# openSX70-bench-new-v2-1.net
KiCad netlist of a schematic drawn in EAGLE
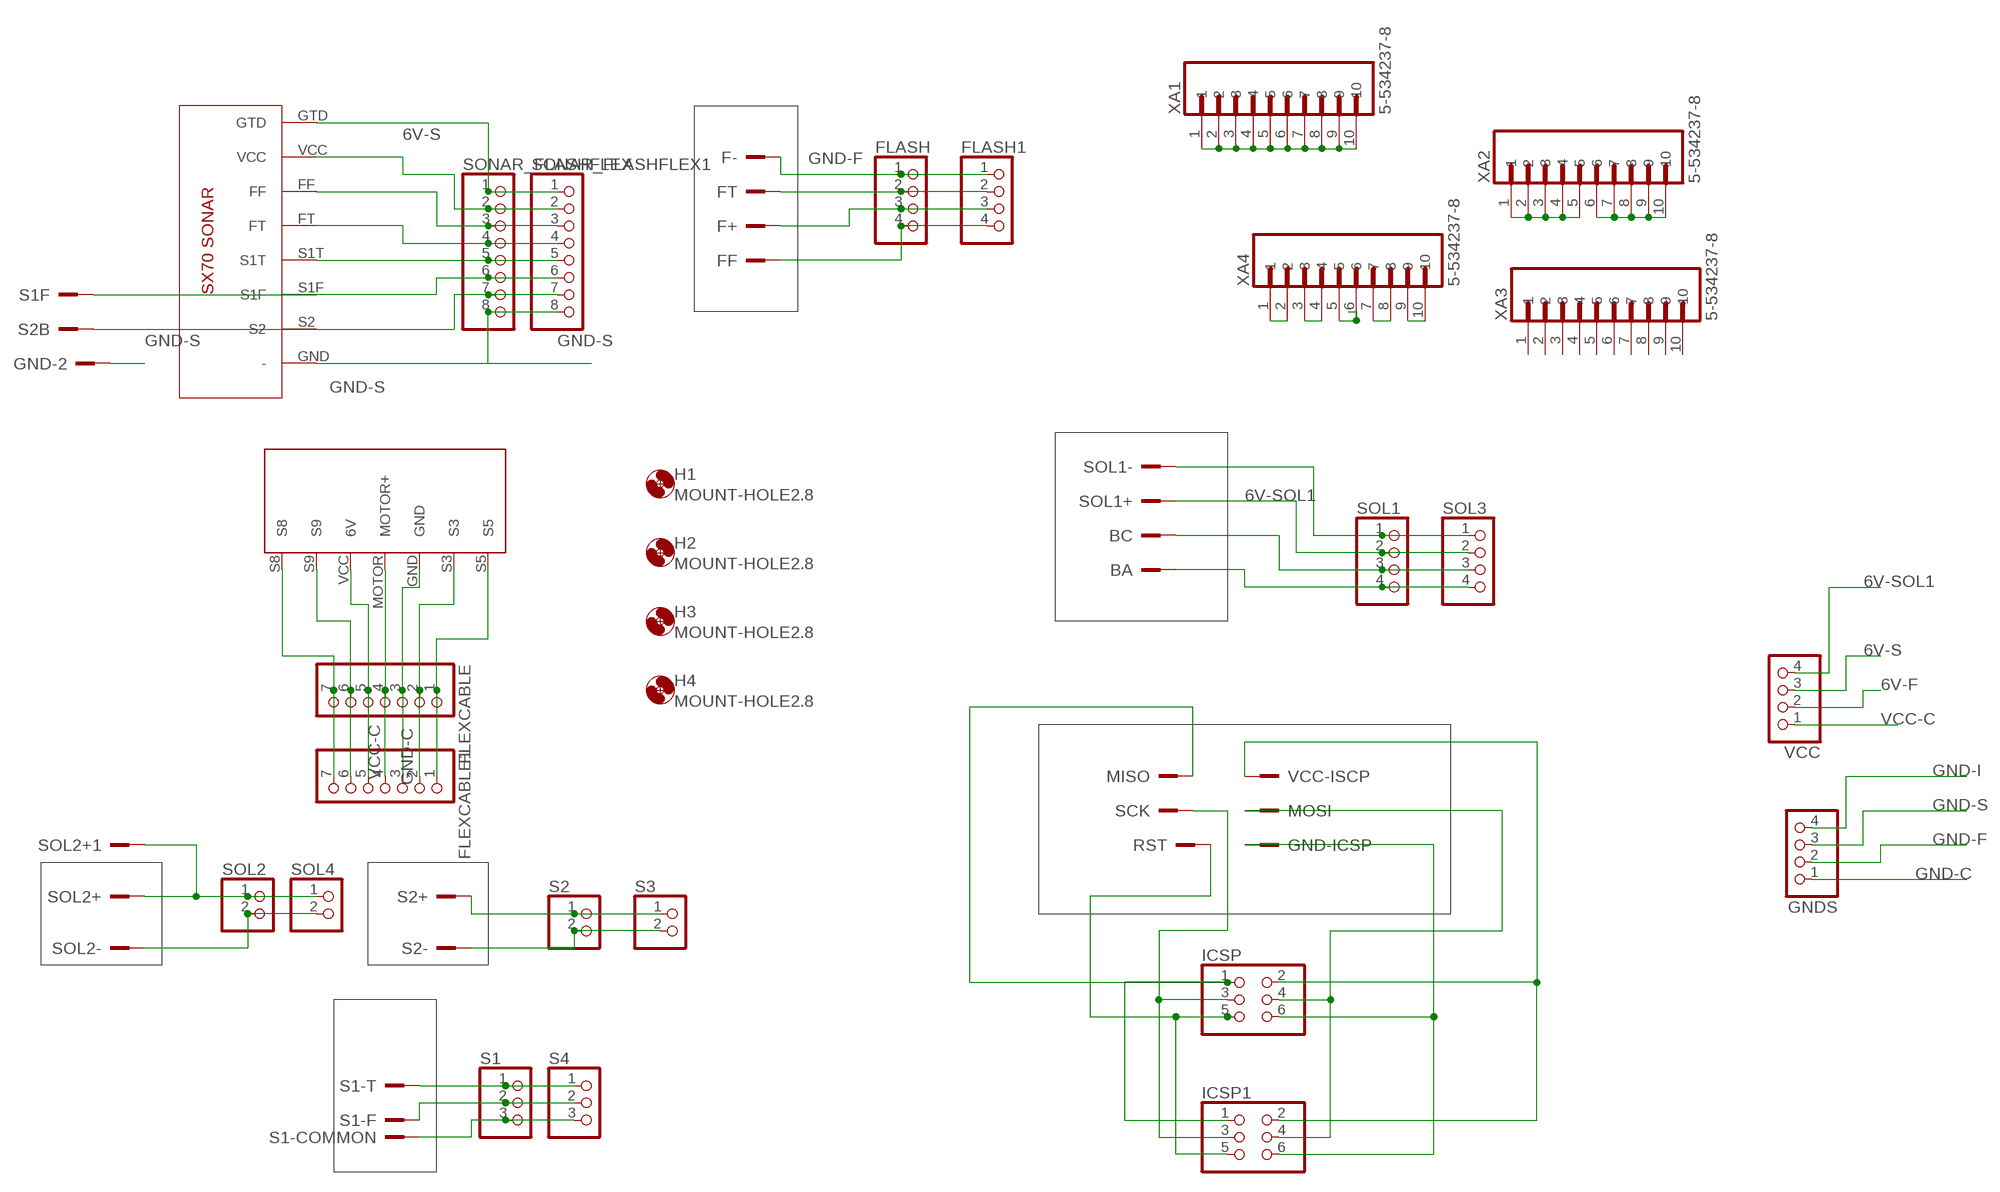
[diagram p0: schematic, sheet 1]

(export (version "E")
  (design (tool "Eeschema 10.0.6"))
  (components
    (comp (ref "BA")
      (value "PINHEAD")
      (footprint "eagle-import:1X01")
      (libsource (lib "eagle-import") (part "PINHEAD"))
    )
    (comp (ref "BC")
      (value "PINHEAD")
      (footprint "eagle-import:1X01")
      (libsource (lib "eagle-import") (part "PINHEAD"))
    )
    (comp (ref "F+")
      (value "PINHEAD")
      (footprint "eagle-import:1X01")
      (libsource (lib "eagle-import") (part "PINHEAD"))
    )
    (comp (ref "F-")
      (value "PINHEAD")
      (footprint "eagle-import:1X01")
      (libsource (lib "eagle-import") (part "PINHEAD"))
    )
    (comp (ref "FF")
      (value "PINHEAD")
      (footprint "eagle-import:1X01")
      (libsource (lib "eagle-import") (part "PINHEAD"))
    )
    (comp (ref "FLASH")
      (value "PINHD-1X4")
      (footprint "eagle-import:1X04")
      (libsource (lib "eagle-import") (part "PINHD-1X4"))
    )
    (comp (ref "FLASH1")
      (value "PINHD-1X4")
      (footprint "eagle-import:1X04")
      (libsource (lib "eagle-import") (part "PINHD-1X4"))
    )
    (comp (ref "FLEXCABLE")
      (value "PINHD-1X7")
      (footprint "eagle-import:1X07")
      (libsource (lib "eagle-import") (part "PINHD-1X7"))
    )
    (comp (ref "FLEXCABLE1")
      (value "PINHD-1X7")
      (footprint "eagle-import:1X07")
      (libsource (lib "eagle-import") (part "PINHD-1X7"))
    )
    (comp (ref "FT")
      (value "PINHEAD")
      (footprint "eagle-import:1X01")
      (libsource (lib "eagle-import") (part "PINHEAD"))
    )
    (comp (ref "GND-2")
      (value "PINHEAD")
      (footprint "eagle-import:1X01")
      (libsource (lib "eagle-import") (part "PINHEAD"))
    )
    (comp (ref "GND-ICSP")
      (value "PINHEAD")
      (footprint "eagle-import:1X01")
      (libsource (lib "eagle-import") (part "PINHEAD"))
    )
    (comp (ref "GNDS")
      (value "PINHD-1X4")
      (footprint "eagle-import:1X04")
      (libsource (lib "eagle-import") (part "PINHD-1X4"))
    )
    (comp (ref "H1")
      (value "MOUNT-HOLE2.8")
      (footprint "eagle-import:2,8")
      (libsource (lib "eagle-import") (part "MOUNT-HOLE2.8"))
    )
    (comp (ref "H2")
      (value "MOUNT-HOLE2.8")
      (footprint "eagle-import:2,8")
      (libsource (lib "eagle-import") (part "MOUNT-HOLE2.8"))
    )
    (comp (ref "H3")
      (value "MOUNT-HOLE2.8")
      (footprint "eagle-import:2,8")
      (libsource (lib "eagle-import") (part "MOUNT-HOLE2.8"))
    )
    (comp (ref "H4")
      (value "MOUNT-HOLE2.8")
      (footprint "eagle-import:2,8")
      (libsource (lib "eagle-import") (part "MOUNT-HOLE2.8"))
    )
    (comp (ref "ICSP")
      (value "PINHD-2X3")
      (footprint "eagle-import:2X03")
      (libsource (lib "eagle-import") (part "PINHD-2X3"))
    )
    (comp (ref "ICSP1")
      (value "PINHD-2X3")
      (footprint "eagle-import:2X03")
      (libsource (lib "eagle-import") (part "PINHD-2X3"))
    )
    (comp (ref "MISO")
      (value "PINHEAD")
      (footprint "eagle-import:1X01")
      (libsource (lib "eagle-import") (part "PINHEAD"))
    )
    (comp (ref "MOSI")
      (value "PINHEAD")
      (footprint "eagle-import:1X01")
      (libsource (lib "eagle-import") (part "PINHEAD"))
    )
    (comp (ref "RST")
      (value "PINHEAD")
      (footprint "eagle-import:1X01")
      (libsource (lib "eagle-import") (part "PINHEAD"))
    )
    (comp (ref "S1")
      (value "PINHD-1X3")
      (footprint "eagle-import:1X03")
      (libsource (lib "eagle-import") (part "PINHD-1X3"))
    )
    (comp (ref "S1-COMMON")
      (value "PINHEAD")
      (footprint "eagle-import:1X01")
      (libsource (lib "eagle-import") (part "PINHEAD"))
    )
    (comp (ref "S1-F")
      (value "PINHEAD")
      (footprint "eagle-import:1X01")
      (libsource (lib "eagle-import") (part "PINHEAD"))
    )
    (comp (ref "S1-T")
      (value "PINHEAD")
      (footprint "eagle-import:1X01")
      (libsource (lib "eagle-import") (part "PINHEAD"))
    )
    (comp (ref "S1F")
      (value "PINHEAD")
      (footprint "eagle-import:1X01")
      (libsource (lib "eagle-import") (part "PINHEAD"))
    )
    (comp (ref "S2")
      (value "PINHD-1X2")
      (footprint "eagle-import:1X02")
      (libsource (lib "eagle-import") (part "PINHD-1X2"))
    )
    (comp (ref "S2+")
      (value "PINHEAD")
      (footprint "eagle-import:1X01")
      (libsource (lib "eagle-import") (part "PINHEAD"))
    )
    (comp (ref "S2-")
      (value "PINHEAD")
      (footprint "eagle-import:1X01")
      (libsource (lib "eagle-import") (part "PINHEAD"))
    )
    (comp (ref "S2B")
      (value "PINHEAD")
      (footprint "eagle-import:1X01")
      (libsource (lib "eagle-import") (part "PINHEAD"))
    )
    (comp (ref "S3")
      (value "PINHD-1X2")
      (footprint "eagle-import:1X02")
      (libsource (lib "eagle-import") (part "PINHD-1X2"))
    )
    (comp (ref "S4")
      (value "PINHD-1X3")
      (footprint "eagle-import:1X03")
      (libsource (lib "eagle-import") (part "PINHD-1X3"))
    )
    (comp (ref "SCK")
      (value "PINHEAD")
      (footprint "eagle-import:1X01")
      (libsource (lib "eagle-import") (part "PINHEAD"))
    )
    (comp (ref "SOL1")
      (value "PINHD-1X4")
      (footprint "eagle-import:1X04")
      (libsource (lib "eagle-import") (part "PINHD-1X4"))
    )
    (comp (ref "SOL1+")
      (value "PINHEAD")
      (footprint "eagle-import:1X01")
      (libsource (lib "eagle-import") (part "PINHEAD"))
    )
    (comp (ref "SOL1-")
      (value "PINHEAD")
      (footprint "eagle-import:1X01")
      (libsource (lib "eagle-import") (part "PINHEAD"))
    )
    (comp (ref "SOL2")
      (value "PINHD-1X2")
      (footprint "eagle-import:1X02")
      (libsource (lib "eagle-import") (part "PINHD-1X2"))
    )
    (comp (ref "SOL2+")
      (value "PINHEAD")
      (footprint "eagle-import:1X01")
      (libsource (lib "eagle-import") (part "PINHEAD"))
    )
    (comp (ref "SOL2+1")
      (value "PINHEAD")
      (footprint "eagle-import:1X01")
      (libsource (lib "eagle-import") (part "PINHEAD"))
    )
    (comp (ref "SOL2-")
      (value "PINHEAD")
      (footprint "eagle-import:1X01")
      (libsource (lib "eagle-import") (part "PINHEAD"))
    )
    (comp (ref "SOL3")
      (value "PINHD-1X4")
      (footprint "eagle-import:1X04")
      (libsource (lib "eagle-import") (part "PINHD-1X4"))
    )
    (comp (ref "SOL4")
      (value "PINHD-1X2")
      (footprint "eagle-import:1X02")
      (libsource (lib "eagle-import") (part "PINHD-1X2"))
    )
    (comp (ref "SONAR_FLASHFLEX")
      (value "PINHD-1X8")
      (footprint "eagle-import:1X08")
      (libsource (lib "eagle-import") (part "PINHD-1X8"))
    )
    (comp (ref "SONAR_FLASHFLEX1")
      (value "PINHD-1X8")
      (footprint "eagle-import:1X08")
      (libsource (lib "eagle-import") (part "PINHD-1X8"))
    )
    (comp (ref "U$1")
      (value "SX70-7-PAD-HOLES-PROPER")
      (footprint "eagle-import:SX70-7-PAD-PROPER-HOLES2")
      (libsource (lib "eagle-import") (part "SX70-7-PAD-HOLES-PROPER"))
    )
    (comp (ref "U$2")
      (value "SX70-SONAR-FLASHFLEX-HOLES")
      (footprint "eagle-import:SONAR-FLASHFLEX-HOLES")
      (libsource (lib "eagle-import") (part "SX70-SONAR-FLASHFLEX-HOLES"))
    )
    (comp (ref "VCC")
      (value "PINHD-1X4")
      (footprint "eagle-import:1X04")
      (libsource (lib "eagle-import") (part "PINHD-1X4"))
    )
    (comp (ref "VCC-ISCP")
      (value "PINHEAD")
      (footprint "eagle-import:1X01")
      (libsource (lib "eagle-import") (part "PINHEAD"))
    )
    (comp (ref "XA1")
      (value "5-534237-8")
      (footprint "eagle-import:TE_5-534237-8")
      (fields (field (name "MANUFACTURER") "TE Connectivity"))
      (libsource (lib "eagle-import") (part "5-534237-8"))
    )
    (comp (ref "XA2")
      (value "5-534237-8")
      (footprint "eagle-import:TE_5-534237-8")
      (fields (field (name "MANUFACTURER") "TE Connectivity"))
      (libsource (lib "eagle-import") (part "5-534237-8"))
    )
    (comp (ref "XA3")
      (value "5-534237-8")
      (footprint "eagle-import:TE_5-534237-8")
      (fields (field (name "MANUFACTURER") "TE Connectivity"))
      (libsource (lib "eagle-import") (part "5-534237-8"))
    )
    (comp (ref "XA4")
      (value "5-534237-8")
      (footprint "eagle-import:TE_5-534237-8")
      (fields (field (name "MANUFACTURER") "TE Connectivity"))
      (libsource (lib "eagle-import") (part "5-534237-8"))
    )
  )
  (nets
    (net (code "1") (name "/6V-F") (class "Default")
      (node (ref "F+") (pin "1") (pinfunction "KL_1") (pintype "passive"))
      (node (ref "FLASH") (pin "3") (pinfunction "3_3") (pintype "passive"))
      (node (ref "FLASH1") (pin "3") (pinfunction "3_3") (pintype "passive"))
      (node (ref "VCC") (pin "2") (pinfunction "2_2") (pintype "passive"))
    )
    (net (code "2") (name "/6V-S") (class "Default")
      (node (ref "SONAR_FLASHFLEX") (pin "2") (pinfunction "2_2") (pintype "passive"))
      (node (ref "SONAR_FLASHFLEX1") (pin "2") (pinfunction "2_2") (pintype "passive"))
      (node (ref "U$2") (pin "VCC") (pinfunction "VCC_VCC") (pintype "bidirectional"))
      (node (ref "VCC") (pin "3") (pinfunction "3_3") (pintype "passive"))
    )
    (net (code "3") (name "/6V-SOL1") (class "Default")
      (node (ref "SOL1") (pin "2") (pinfunction "2_2") (pintype "passive"))
      (node (ref "SOL1+") (pin "1") (pinfunction "KL_1") (pintype "passive"))
      (node (ref "SOL3") (pin "2") (pinfunction "2_2") (pintype "passive"))
      (node (ref "VCC") (pin "4") (pinfunction "4_4") (pintype "passive"))
    )
    (net (code "4") (name "/GND-C") (class "Default")
      (node (ref "FLEXCABLE") (pin "3") (pinfunction "3_3") (pintype "passive"))
      (node (ref "FLEXCABLE1") (pin "3") (pinfunction "3_3") (pintype "passive"))
      (node (ref "GNDS") (pin "1") (pinfunction "1_1") (pintype "passive"))
      (node (ref "U$1") (pin "GND") (pinfunction "GND_GND") (pintype "bidirectional"))
    )
    (net (code "5") (name "/GND-F") (class "Default")
      (node (ref "F-") (pin "1") (pinfunction "KL_1") (pintype "passive"))
      (node (ref "FLASH") (pin "1") (pinfunction "1_1") (pintype "passive"))
      (node (ref "FLASH1") (pin "1") (pinfunction "1_1") (pintype "passive"))
      (node (ref "GNDS") (pin "2") (pinfunction "2_2") (pintype "passive"))
    )
    (net (code "6") (name "/GND-I") (class "Default")
      (node (ref "GND-ICSP") (pin "1") (pinfunction "KL_1") (pintype "passive"))
      (node (ref "GNDS") (pin "4") (pinfunction "4_4") (pintype "passive"))
      (node (ref "ICSP") (pin "6") (pinfunction "6_6") (pintype "passive"))
      (node (ref "ICSP1") (pin "6") (pinfunction "6_6") (pintype "passive"))
    )
    (net (code "7") (name "/GND-S") (class "Default")
      (node (ref "GND-2") (pin "1") (pinfunction "KL_1") (pintype "passive"))
      (node (ref "GNDS") (pin "3") (pinfunction "3_3") (pintype "passive"))
      (node (ref "SONAR_FLASHFLEX") (pin "8") (pinfunction "8_8") (pintype "passive"))
      (node (ref "SONAR_FLASHFLEX1") (pin "8") (pinfunction "8_8") (pintype "passive"))
      (node (ref "U$2") (pin "GND") (pinfunction "-_GND") (pintype "bidirectional"))
    )
    (net (code "8") (name "/VCC-C") (class "Default")
      (node (ref "FLEXCABLE") (pin "5") (pinfunction "5_5") (pintype "passive"))
      (node (ref "FLEXCABLE1") (pin "5") (pinfunction "5_5") (pintype "passive"))
      (node (ref "U$1") (pin "VCC") (pinfunction "6V_VCC") (pintype "bidirectional"))
      (node (ref "VCC") (pin "1") (pinfunction "1_1") (pintype "passive"))
    )
    (net (code "9") (name "Net-(BA-KL)") (class "Default")
      (node (ref "BA") (pin "1") (pinfunction "KL_1") (pintype "passive"))
      (node (ref "SOL1") (pin "4") (pinfunction "4_4") (pintype "passive"))
      (node (ref "SOL3") (pin "4") (pinfunction "4_4") (pintype "passive"))
    )
    (net (code "10") (name "Net-(BC-KL)") (class "Default")
      (node (ref "BC") (pin "1") (pinfunction "KL_1") (pintype "passive"))
      (node (ref "SOL1") (pin "3") (pinfunction "3_3") (pintype "passive"))
      (node (ref "SOL3") (pin "3") (pinfunction "3_3") (pintype "passive"))
    )
    (net (code "11") (name "Net-(FF-KL)") (class "Default")
      (node (ref "FF") (pin "1") (pinfunction "KL_1") (pintype "passive"))
      (node (ref "FLASH") (pin "4") (pinfunction "4_4") (pintype "passive"))
      (node (ref "FLASH1") (pin "4") (pinfunction "4_4") (pintype "passive"))
    )
    (net (code "12") (name "Net-(FLEXCABLE-Pad1)") (class "Default")
      (node (ref "FLEXCABLE") (pin "1") (pinfunction "1_1") (pintype "passive"))
      (node (ref "FLEXCABLE1") (pin "1") (pinfunction "1_1") (pintype "passive"))
      (node (ref "U$1") (pin "S5") (pinfunction "S5_S5") (pintype "bidirectional"))
    )
    (net (code "13") (name "Net-(FLEXCABLE-Pad2)") (class "Default")
      (node (ref "FLEXCABLE") (pin "2") (pinfunction "2_2") (pintype "passive"))
      (node (ref "FLEXCABLE1") (pin "2") (pinfunction "2_2") (pintype "passive"))
      (node (ref "U$1") (pin "S3") (pinfunction "S3_S3") (pintype "bidirectional"))
    )
    (net (code "14") (name "Net-(FLEXCABLE-Pad6)") (class "Default")
      (node (ref "FLEXCABLE") (pin "6") (pinfunction "6_6") (pintype "passive"))
      (node (ref "FLEXCABLE1") (pin "6") (pinfunction "6_6") (pintype "passive"))
      (node (ref "U$1") (pin "S9") (pinfunction "S9_S9") (pintype "bidirectional"))
    )
    (net (code "15") (name "Net-(FLEXCABLE-Pad7)") (class "Default")
      (node (ref "FLEXCABLE") (pin "7") (pinfunction "7_7") (pintype "passive"))
      (node (ref "FLEXCABLE1") (pin "7") (pinfunction "7_7") (pintype "passive"))
      (node (ref "U$1") (pin "S8") (pinfunction "S8_S8") (pintype "bidirectional"))
    )
    (net (code "16") (name "Net-(FT-KL)") (class "Default")
      (node (ref "FLASH") (pin "2") (pinfunction "2_2") (pintype "passive"))
      (node (ref "FLASH1") (pin "2") (pinfunction "2_2") (pintype "passive"))
      (node (ref "FT") (pin "1") (pinfunction "KL_1") (pintype "passive"))
    )
    (net (code "17") (name "Net-(MISO-KL)") (class "Default")
      (node (ref "ICSP") (pin "1") (pinfunction "1_1") (pintype "passive"))
      (node (ref "ICSP1") (pin "1") (pinfunction "1_1") (pintype "passive"))
      (node (ref "MISO") (pin "1") (pinfunction "KL_1") (pintype "passive"))
    )
    (net (code "18") (name "Net-(MOSI-KL)") (class "Default")
      (node (ref "ICSP") (pin "4") (pinfunction "4_4") (pintype "passive"))
      (node (ref "ICSP1") (pin "4") (pinfunction "4_4") (pintype "passive"))
      (node (ref "MOSI") (pin "1") (pinfunction "KL_1") (pintype "passive"))
    )
    (net (code "19") (name "Net-(RST-KL)") (class "Default")
      (node (ref "ICSP") (pin "5") (pinfunction "5_5") (pintype "passive"))
      (node (ref "ICSP1") (pin "5") (pinfunction "5_5") (pintype "passive"))
      (node (ref "RST") (pin "1") (pinfunction "KL_1") (pintype "passive"))
    )
    (net (code "20") (name "Net-(S1-COMMON-KL)") (class "Default")
      (node (ref "S1") (pin "3") (pinfunction "3_3") (pintype "passive"))
      (node (ref "S1-COMMON") (pin "1") (pinfunction "KL_1") (pintype "passive"))
      (node (ref "S4") (pin "3") (pinfunction "3_3") (pintype "passive"))
    )
    (net (code "21") (name "Net-(S1-F-KL)") (class "Default")
      (node (ref "S1") (pin "2") (pinfunction "2_2") (pintype "passive"))
      (node (ref "S1-F") (pin "1") (pinfunction "KL_1") (pintype "passive"))
      (node (ref "S4") (pin "2") (pinfunction "2_2") (pintype "passive"))
    )
    (net (code "22") (name "Net-(S1-T-KL)") (class "Default")
      (node (ref "S1") (pin "1") (pinfunction "1_1") (pintype "passive"))
      (node (ref "S1-T") (pin "1") (pinfunction "KL_1") (pintype "passive"))
      (node (ref "S4") (pin "1") (pinfunction "1_1") (pintype "passive"))
    )
    (net (code "23") (name "Net-(S1F-KL)") (class "Default")
      (node (ref "S1F") (pin "1") (pinfunction "KL_1") (pintype "passive"))
      (node (ref "SONAR_FLASHFLEX") (pin "6") (pinfunction "6_6") (pintype "passive"))
      (node (ref "SONAR_FLASHFLEX1") (pin "6") (pinfunction "6_6") (pintype "passive"))
      (node (ref "U$2") (pin "S1F") (pinfunction "S1F_S1F") (pintype "bidirectional"))
    )
    (net (code "24") (name "Net-(S2+-KL)") (class "Default")
      (node (ref "S2") (pin "1") (pinfunction "1_1") (pintype "passive"))
      (node (ref "S2+") (pin "1") (pinfunction "KL_1") (pintype "passive"))
      (node (ref "S3") (pin "1") (pinfunction "1_1") (pintype "passive"))
    )
    (net (code "25") (name "Net-(S2--KL)") (class "Default")
      (node (ref "S2") (pin "2") (pinfunction "2_2") (pintype "passive"))
      (node (ref "S2-") (pin "1") (pinfunction "KL_1") (pintype "passive"))
      (node (ref "S3") (pin "2") (pinfunction "2_2") (pintype "passive"))
    )
    (net (code "26") (name "Net-(S2B-KL)") (class "Default")
      (node (ref "S2B") (pin "1") (pinfunction "KL_1") (pintype "passive"))
      (node (ref "SONAR_FLASHFLEX") (pin "7") (pinfunction "7_7") (pintype "passive"))
      (node (ref "SONAR_FLASHFLEX1") (pin "7") (pinfunction "7_7") (pintype "passive"))
      (node (ref "U$2") (pin "S2") (pinfunction "S2_S2") (pintype "bidirectional"))
    )
    (net (code "27") (name "Net-(SCK-KL)") (class "Default")
      (node (ref "ICSP") (pin "3") (pinfunction "3_3") (pintype "passive"))
      (node (ref "ICSP1") (pin "3") (pinfunction "3_3") (pintype "passive"))
      (node (ref "SCK") (pin "1") (pinfunction "KL_1") (pintype "passive"))
    )
    (net (code "28") (name "Net-(SOL1--KL)") (class "Default")
      (node (ref "SOL1") (pin "1") (pinfunction "1_1") (pintype "passive"))
      (node (ref "SOL1-") (pin "1") (pinfunction "KL_1") (pintype "passive"))
      (node (ref "SOL3") (pin "1") (pinfunction "1_1") (pintype "passive"))
    )
    (net (code "29") (name "Net-(SOL2+-KL)") (class "Default")
      (node (ref "SOL2") (pin "1") (pinfunction "1_1") (pintype "passive"))
      (node (ref "SOL2+") (pin "1") (pinfunction "KL_1") (pintype "passive"))
      (node (ref "SOL2+1") (pin "1") (pinfunction "KL_1") (pintype "passive"))
      (node (ref "SOL4") (pin "1") (pinfunction "1_1") (pintype "passive"))
    )
    (net (code "30") (name "Net-(SOL2--KL)") (class "Default")
      (node (ref "SOL2") (pin "2") (pinfunction "2_2") (pintype "passive"))
      (node (ref "SOL2-") (pin "1") (pinfunction "KL_1") (pintype "passive"))
      (node (ref "SOL4") (pin "2") (pinfunction "2_2") (pintype "passive"))
    )
    (net (code "31") (name "Net-(SONAR_FLASHFLEX-Pad1)") (class "Default")
      (node (ref "SONAR_FLASHFLEX") (pin "1") (pinfunction "1_1") (pintype "passive"))
      (node (ref "SONAR_FLASHFLEX1") (pin "1") (pinfunction "1_1") (pintype "passive"))
      (node (ref "U$2") (pin "GTD") (pinfunction "GTD_GTD") (pintype "bidirectional"))
    )
    (net (code "32") (name "Net-(SONAR_FLASHFLEX-Pad3)") (class "Default")
      (node (ref "SONAR_FLASHFLEX") (pin "3") (pinfunction "3_3") (pintype "passive"))
      (node (ref "SONAR_FLASHFLEX1") (pin "3") (pinfunction "3_3") (pintype "passive"))
      (node (ref "U$2") (pin "FF") (pinfunction "FF_FF") (pintype "bidirectional"))
    )
    (net (code "33") (name "Net-(SONAR_FLASHFLEX-Pad4)") (class "Default")
      (node (ref "SONAR_FLASHFLEX") (pin "4") (pinfunction "4_4") (pintype "passive"))
      (node (ref "SONAR_FLASHFLEX1") (pin "4") (pinfunction "4_4") (pintype "passive"))
      (node (ref "U$2") (pin "FT") (pinfunction "FT_FT") (pintype "bidirectional"))
    )
    (net (code "34") (name "Net-(SONAR_FLASHFLEX-Pad5)") (class "Default")
      (node (ref "SONAR_FLASHFLEX") (pin "5") (pinfunction "5_5") (pintype "passive"))
      (node (ref "SONAR_FLASHFLEX1") (pin "5") (pinfunction "5_5") (pintype "passive"))
      (node (ref "U$2") (pin "S1T") (pinfunction "S1T_S1T") (pintype "bidirectional"))
    )
    (net (code "35") (name "Net-(U$1-MOTOR+)") (class "Default")
      (node (ref "FLEXCABLE") (pin "4") (pinfunction "4_4") (pintype "passive"))
      (node (ref "FLEXCABLE1") (pin "4") (pinfunction "4_4") (pintype "passive"))
      (node (ref "U$1") (pin "MOTOR") (pinfunction "MOTOR+_MOTOR") (pintype "bidirectional"))
    )
    (net (code "36") (name "Net-(VCC-ISCP-KL)") (class "Default")
      (node (ref "ICSP") (pin "2") (pinfunction "2_2") (pintype "passive"))
      (node (ref "ICSP1") (pin "2") (pinfunction "2_2") (pintype "passive"))
      (node (ref "VCC-ISCP") (pin "1") (pinfunction "KL_1") (pintype "passive"))
    )
    (net (code "37") (name "Net-(XA1-Pad1)") (class "Default")
      (node (ref "XA1") (pin "1") (pinfunction "1_1") (pintype "passive"))
      (node (ref "XA1") (pin "10") (pinfunction "10_10") (pintype "passive"))
      (node (ref "XA1") (pin "2") (pinfunction "2_2") (pintype "passive"))
      (node (ref "XA1") (pin "3") (pinfunction "3_3") (pintype "passive"))
      (node (ref "XA1") (pin "4") (pinfunction "4_4") (pintype "passive"))
      (node (ref "XA1") (pin "5") (pinfunction "5_5") (pintype "passive"))
      (node (ref "XA1") (pin "6") (pinfunction "6_6") (pintype "passive"))
      (node (ref "XA1") (pin "7") (pinfunction "7_7") (pintype "passive"))
      (node (ref "XA1") (pin "8") (pinfunction "8_8") (pintype "passive"))
      (node (ref "XA1") (pin "9") (pinfunction "9_9") (pintype "passive"))
    )
    (net (code "38") (name "Net-(XA2-Pad1)") (class "Default")
      (node (ref "XA2") (pin "1") (pinfunction "1_1") (pintype "passive"))
      (node (ref "XA2") (pin "2") (pinfunction "2_2") (pintype "passive"))
      (node (ref "XA2") (pin "3") (pinfunction "3_3") (pintype "passive"))
      (node (ref "XA2") (pin "4") (pinfunction "4_4") (pintype "passive"))
      (node (ref "XA2") (pin "5") (pinfunction "5_5") (pintype "passive"))
    )
    (net (code "39") (name "Net-(XA2-Pad10)") (class "Default")
      (node (ref "XA2") (pin "10") (pinfunction "10_10") (pintype "passive"))
      (node (ref "XA2") (pin "6") (pinfunction "6_6") (pintype "passive"))
      (node (ref "XA2") (pin "7") (pinfunction "7_7") (pintype "passive"))
      (node (ref "XA2") (pin "8") (pinfunction "8_8") (pintype "passive"))
      (node (ref "XA2") (pin "9") (pinfunction "9_9") (pintype "passive"))
    )
    (net (code "40") (name "Net-(XA4-Pad1)") (class "Default")
      (node (ref "XA4") (pin "1") (pinfunction "1_1") (pintype "passive"))
      (node (ref "XA4") (pin "2") (pinfunction "2_2") (pintype "passive"))
    )
    (net (code "41") (name "Net-(XA4-Pad3)") (class "Default")
      (node (ref "XA4") (pin "3") (pinfunction "3_3") (pintype "passive"))
      (node (ref "XA4") (pin "4") (pinfunction "4_4") (pintype "passive"))
    )
    (net (code "42") (name "Net-(XA4-Pad5)") (class "Default")
      (node (ref "XA4") (pin "5") (pinfunction "5_5") (pintype "passive"))
      (node (ref "XA4") (pin "6") (pinfunction "6_6") (pintype "passive"))
    )
    (net (code "43") (name "Net-(XA4-Pad7)") (class "Default")
      (node (ref "XA4") (pin "7") (pinfunction "7_7") (pintype "passive"))
      (node (ref "XA4") (pin "8") (pinfunction "8_8") (pintype "passive"))
    )
    (net (code "44") (name "Net-(XA4-Pad10)") (class "Default")
      (node (ref "XA4") (pin "10") (pinfunction "10_10") (pintype "passive"))
      (node (ref "XA4") (pin "9") (pinfunction "9_9") (pintype "passive"))
    )
    (net (code "45") (name "unconnected-(XA3-Pad1)") (class "Default")
      (node (ref "XA3") (pin "1") (pinfunction "1_1") (pintype "passive"))
    )
    (net (code "46") (name "unconnected-(XA3-Pad2)") (class "Default")
      (node (ref "XA3") (pin "2") (pinfunction "2_2") (pintype "passive"))
    )
    (net (code "47") (name "unconnected-(XA3-Pad3)") (class "Default")
      (node (ref "XA3") (pin "3") (pinfunction "3_3") (pintype "passive"))
    )
    (net (code "48") (name "unconnected-(XA3-Pad4)") (class "Default")
      (node (ref "XA3") (pin "4") (pinfunction "4_4") (pintype "passive"))
    )
    (net (code "49") (name "unconnected-(XA3-Pad5)") (class "Default")
      (node (ref "XA3") (pin "5") (pinfunction "5_5") (pintype "passive"))
    )
    (net (code "50") (name "unconnected-(XA3-Pad6)") (class "Default")
      (node (ref "XA3") (pin "6") (pinfunction "6_6") (pintype "passive"))
    )
    (net (code "51") (name "unconnected-(XA3-Pad7)") (class "Default")
      (node (ref "XA3") (pin "7") (pinfunction "7_7") (pintype "passive"))
    )
    (net (code "52") (name "unconnected-(XA3-Pad8)") (class "Default")
      (node (ref "XA3") (pin "8") (pinfunction "8_8") (pintype "passive"))
    )
    (net (code "53") (name "unconnected-(XA3-Pad9)") (class "Default")
      (node (ref "XA3") (pin "9") (pinfunction "9_9") (pintype "passive"))
    )
    (net (code "54") (name "unconnected-(XA3-Pad10)") (class "Default")
      (node (ref "XA3") (pin "10") (pinfunction "10_10") (pintype "passive"))
    )
  )
)
